# Debug-unit_rev01.net
KiCad netlist of a schematic drawn in EAGLE
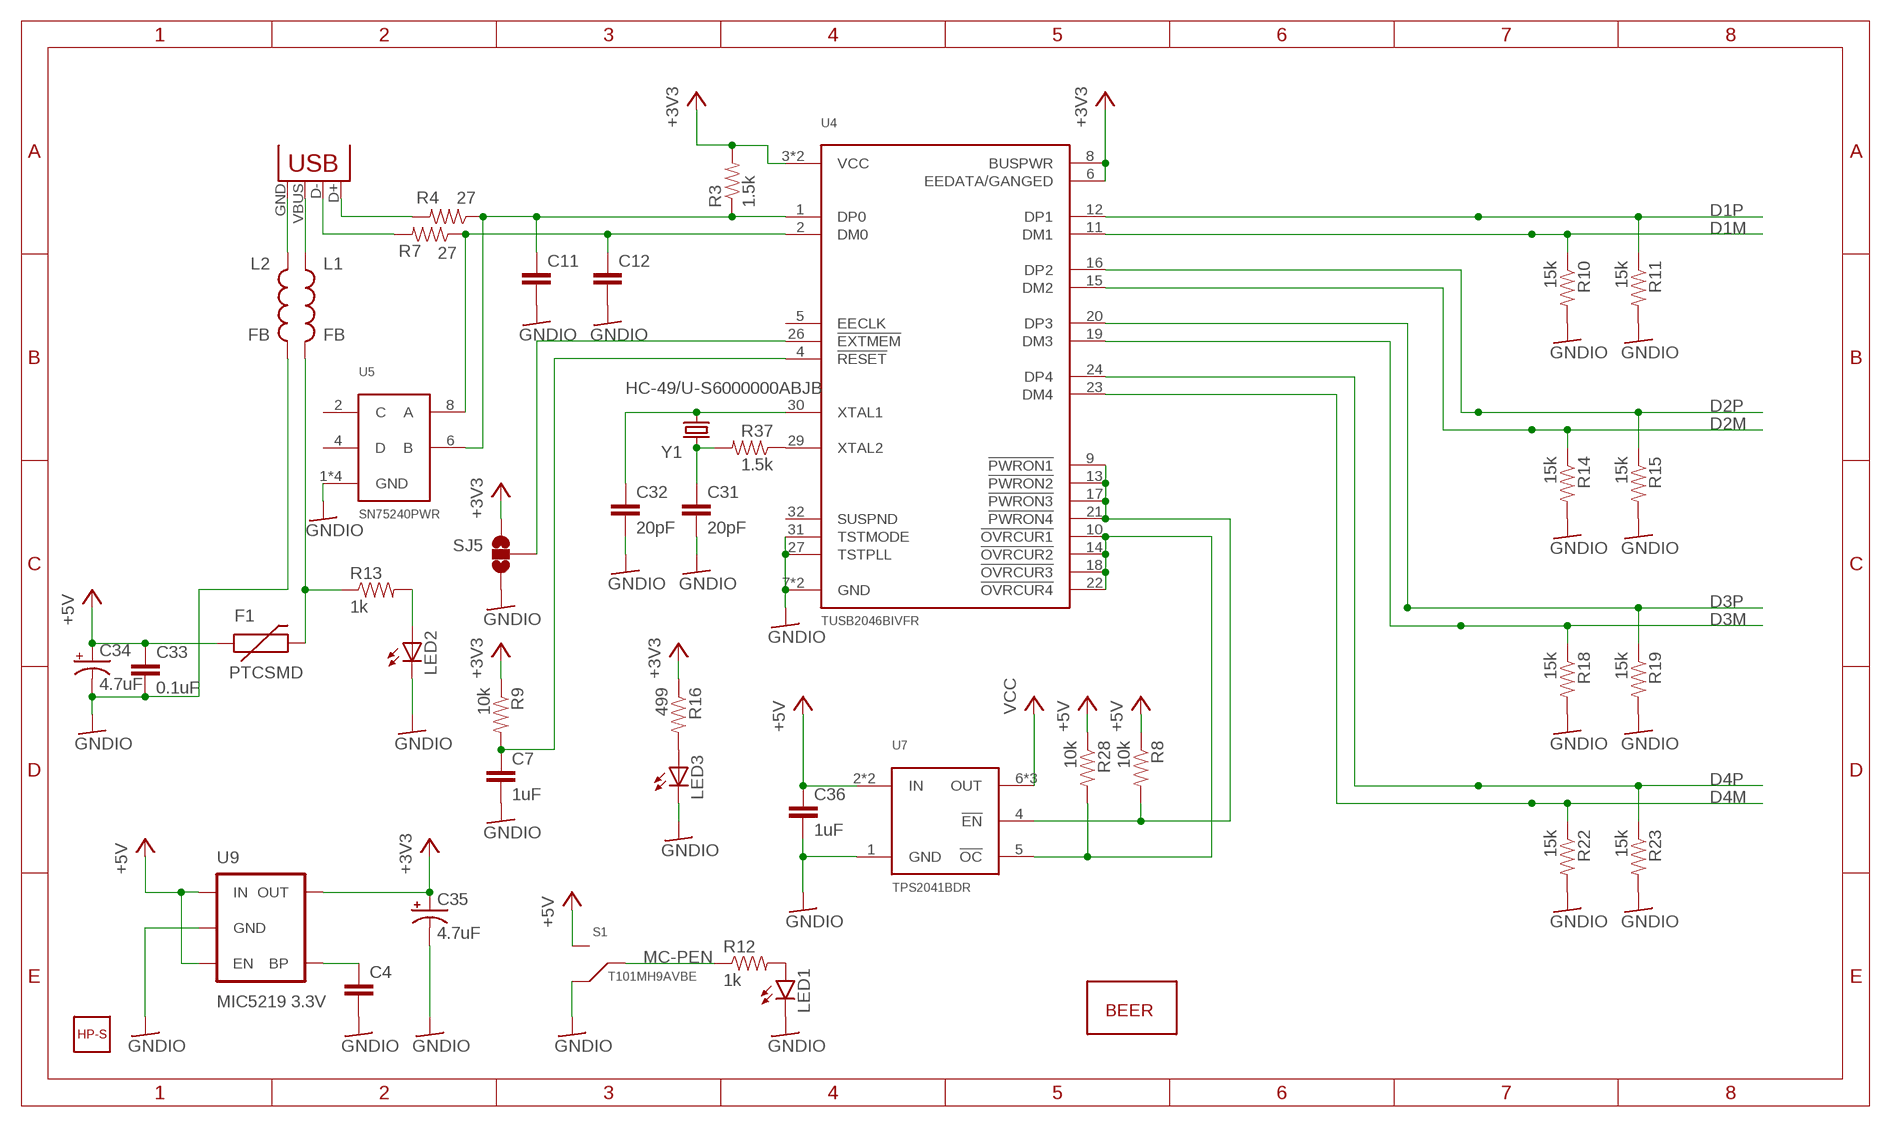
[diagram p0: schematic, sheet 1]
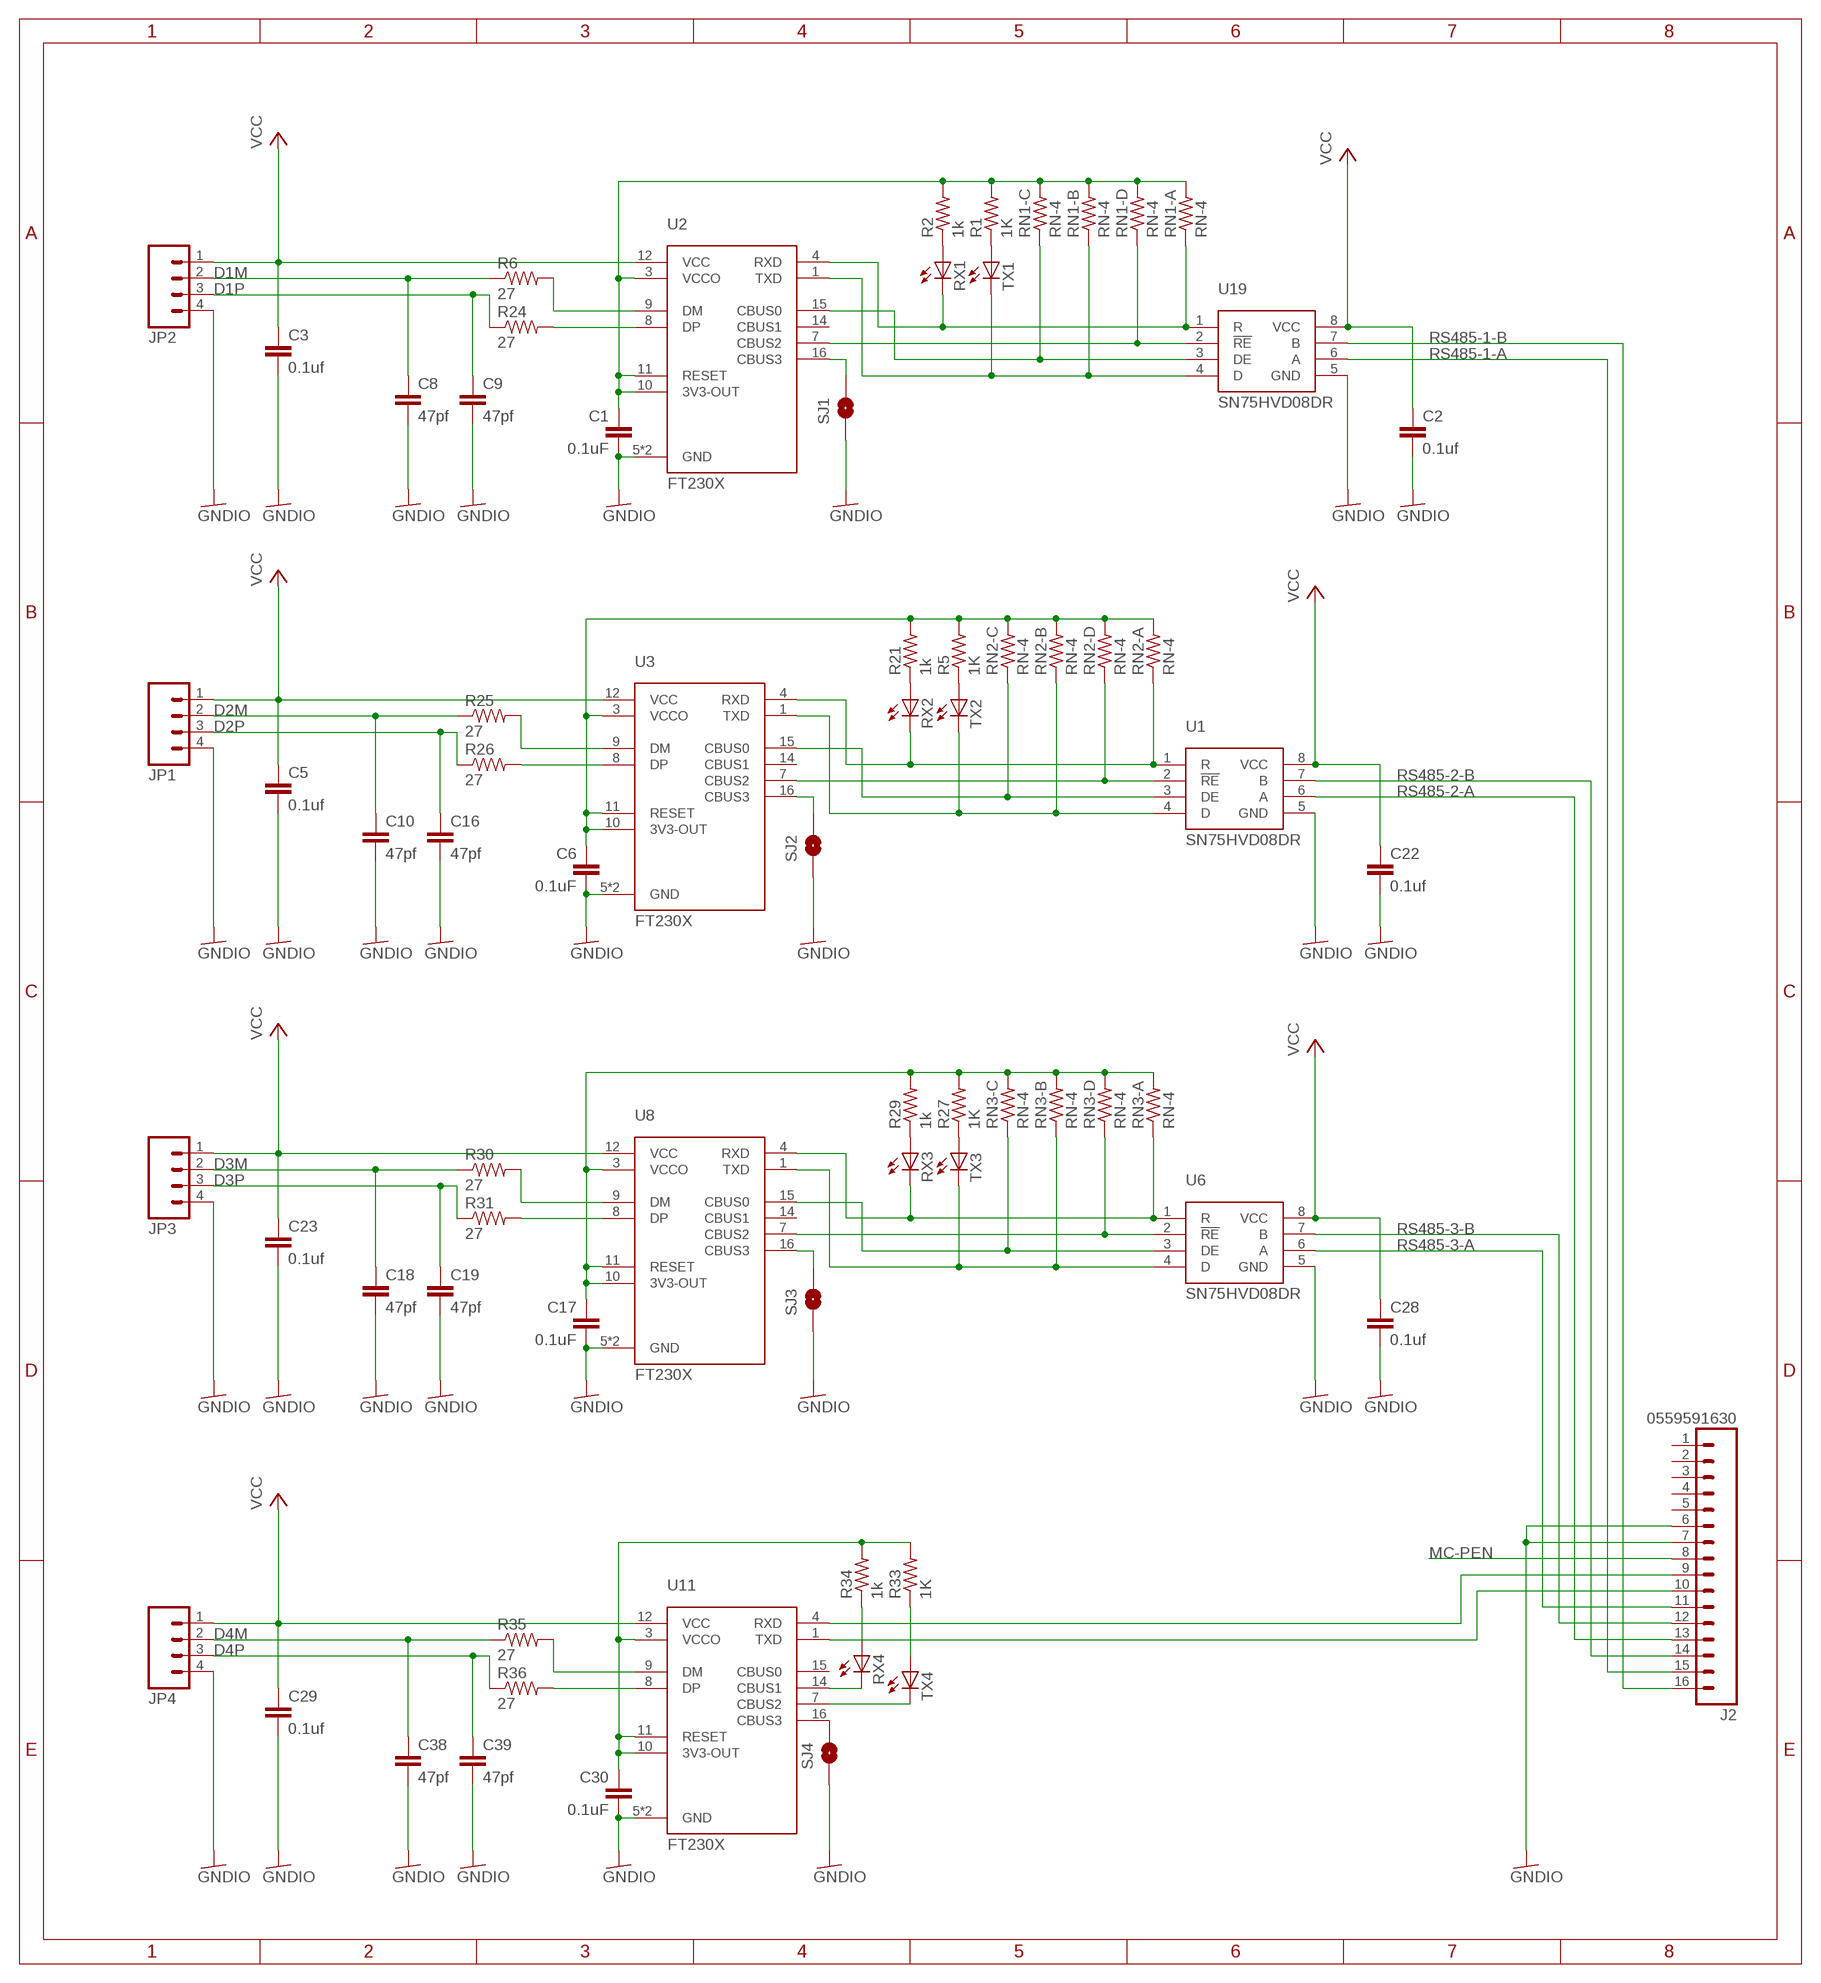
[diagram p1: schematic, sheet 2]

(export (version "E")
  (design (tool "Eeschema 10.0.6"))
  (components
    (comp (ref "C1")
      (value "0.1uF")
      (footprint "eagle-import:0805")
      (libsource (lib "eagle-import") (part "CAP0805"))
    )
    (comp (ref "C2")
      (value "0.1uf")
      (footprint "eagle-import:0805")
      (libsource (lib "eagle-import") (part "CAP0805"))
    )
    (comp (ref "C3")
      (value "0.1uf")
      (footprint "eagle-import:0805")
      (libsource (lib "eagle-import") (part "CAP0805"))
    )
    (comp (ref "C5")
      (value "0.1uf")
      (footprint "eagle-import:0805")
      (libsource (lib "eagle-import") (part "CAP0805"))
    )
    (comp (ref "C6")
      (value "0.1uF")
      (footprint "eagle-import:0805")
      (libsource (lib "eagle-import") (part "CAP0805"))
    )
    (comp (ref "C8")
      (value "47pf")
      (footprint "eagle-import:0805")
      (libsource (lib "eagle-import") (part "CAP0805"))
    )
    (comp (ref "C9")
      (value "47pf")
      (footprint "eagle-import:0805")
      (libsource (lib "eagle-import") (part "CAP0805"))
    )
    (comp (ref "C10")
      (value "47pf")
      (footprint "eagle-import:0805")
      (libsource (lib "eagle-import") (part "CAP0805"))
    )
    (comp (ref "C16")
      (value "47pf")
      (footprint "eagle-import:0805")
      (libsource (lib "eagle-import") (part "CAP0805"))
    )
    (comp (ref "C17")
      (value "0.1uF")
      (footprint "eagle-import:0805")
      (libsource (lib "eagle-import") (part "CAP0805"))
    )
    (comp (ref "C18")
      (value "47pf")
      (footprint "eagle-import:0805")
      (libsource (lib "eagle-import") (part "CAP0805"))
    )
    (comp (ref "C19")
      (value "47pf")
      (footprint "eagle-import:0805")
      (libsource (lib "eagle-import") (part "CAP0805"))
    )
    (comp (ref "C22")
      (value "0.1uf")
      (footprint "eagle-import:0805")
      (libsource (lib "eagle-import") (part "CAP0805"))
    )
    (comp (ref "C23")
      (value "0.1uf")
      (footprint "eagle-import:0805")
      (libsource (lib "eagle-import") (part "CAP0805"))
    )
    (comp (ref "C28")
      (value "0.1uf")
      (footprint "eagle-import:0805")
      (libsource (lib "eagle-import") (part "CAP0805"))
    )
    (comp (ref "C29")
      (value "0.1uf")
      (footprint "eagle-import:0805")
      (libsource (lib "eagle-import") (part "CAP0805"))
    )
    (comp (ref "C30")
      (value "0.1uF")
      (footprint "eagle-import:0805")
      (libsource (lib "eagle-import") (part "CAP0805"))
    )
    (comp (ref "C38")
      (value "47pf")
      (footprint "eagle-import:0805")
      (libsource (lib "eagle-import") (part "CAP0805"))
    )
    (comp (ref "C39")
      (value "47pf")
      (footprint "eagle-import:0805")
      (libsource (lib "eagle-import") (part "CAP0805"))
    )
    (comp (ref "J2")
      (value "0559591630")
      (footprint "eagle-import:0559591630")
      (libsource (lib "eagle-import") (part "0559591630"))
    )
    (comp (ref "JP1")
      (value "M04POLAR_LOCK")
      (footprint "eagle-import:MOLEX-1X4_LOCK")
      (libsource (lib "eagle-import") (part "M04POLAR_LOCK"))
    )
    (comp (ref "JP2")
      (value "M04POLAR_LOCK")
      (footprint "eagle-import:MOLEX-1X4_LOCK")
      (libsource (lib "eagle-import") (part "M04POLAR_LOCK"))
    )
    (comp (ref "JP3")
      (value "M04POLAR_LOCK")
      (footprint "eagle-import:MOLEX-1X4_LOCK")
      (libsource (lib "eagle-import") (part "M04POLAR_LOCK"))
    )
    (comp (ref "JP4")
      (value "M04POLAR_LOCK")
      (footprint "eagle-import:MOLEX-1X4_LOCK")
      (libsource (lib "eagle-import") (part "M04POLAR_LOCK"))
    )
    (comp (ref "R1")
      (value "1K")
      (footprint "eagle-import:R0805")
      (libsource (lib "eagle-import") (part "R-US_R0805"))
    )
    (comp (ref "R2")
      (value "1k")
      (footprint "eagle-import:R0805")
      (libsource (lib "eagle-import") (part "R-US_R0805"))
    )
    (comp (ref "R5")
      (value "1K")
      (footprint "eagle-import:R0805")
      (libsource (lib "eagle-import") (part "R-US_R0805"))
    )
    (comp (ref "R6")
      (value "27")
      (footprint "eagle-import:0805")
      (libsource (lib "eagle-import") (part "RESISTOR0805-RES"))
    )
    (comp (ref "R21")
      (value "1k")
      (footprint "eagle-import:R0805")
      (libsource (lib "eagle-import") (part "R-US_R0805"))
    )
    (comp (ref "R24")
      (value "27")
      (footprint "eagle-import:0805")
      (libsource (lib "eagle-import") (part "RESISTOR0805-RES"))
    )
    (comp (ref "R25")
      (value "27")
      (footprint "eagle-import:0805")
      (libsource (lib "eagle-import") (part "RESISTOR0805-RES"))
    )
    (comp (ref "R26")
      (value "27")
      (footprint "eagle-import:0805")
      (libsource (lib "eagle-import") (part "RESISTOR0805-RES"))
    )
    (comp (ref "R27")
      (value "1K")
      (footprint "eagle-import:R0805")
      (libsource (lib "eagle-import") (part "R-US_R0805"))
    )
    (comp (ref "R29")
      (value "1k")
      (footprint "eagle-import:R0805")
      (libsource (lib "eagle-import") (part "R-US_R0805"))
    )
    (comp (ref "R30")
      (value "27")
      (footprint "eagle-import:0805")
      (libsource (lib "eagle-import") (part "RESISTOR0805-RES"))
    )
    (comp (ref "R31")
      (value "27")
      (footprint "eagle-import:0805")
      (libsource (lib "eagle-import") (part "RESISTOR0805-RES"))
    )
    (comp (ref "R33")
      (value "1K")
      (footprint "eagle-import:R0805")
      (libsource (lib "eagle-import") (part "R-US_R0805"))
    )
    (comp (ref "R34")
      (value "1k")
      (footprint "eagle-import:R0805")
      (libsource (lib "eagle-import") (part "R-US_R0805"))
    )
    (comp (ref "R35")
      (value "27")
      (footprint "eagle-import:0805")
      (libsource (lib "eagle-import") (part "RESISTOR0805-RES"))
    )
    (comp (ref "R36")
      (value "27")
      (footprint "eagle-import:0805")
      (libsource (lib "eagle-import") (part "RESISTOR0805-RES"))
    )
    (comp (ref "RN1")
      (value "RN-4")
      (footprint "eagle-import:CRA06S")
      (libsource (lib "eagle-import") (part "RN-4"))
    )
    (comp (ref "RN2")
      (value "RN-4")
      (footprint "eagle-import:CRA06S")
      (libsource (lib "eagle-import") (part "RN-4"))
    )
    (comp (ref "RN3")
      (value "RN-4")
      (footprint "eagle-import:CRA06S")
      (libsource (lib "eagle-import") (part "RN-4"))
    )
    (comp (ref "RX1")
      (value "LEDCHIPLED_0805")
      (footprint "eagle-import:CHIPLED_0805")
      (libsource (lib "eagle-import") (part "LEDCHIPLED_0805"))
    )
    (comp (ref "RX2")
      (value "LEDCHIPLED_0805")
      (footprint "eagle-import:CHIPLED_0805")
      (libsource (lib "eagle-import") (part "LEDCHIPLED_0805"))
    )
    (comp (ref "RX3")
      (value "LEDCHIPLED_0805")
      (footprint "eagle-import:CHIPLED_0805")
      (libsource (lib "eagle-import") (part "LEDCHIPLED_0805"))
    )
    (comp (ref "RX4")
      (value "LEDCHIPLED_0805")
      (footprint "eagle-import:CHIPLED_0805")
      (libsource (lib "eagle-import") (part "LEDCHIPLED_0805"))
    )
    (comp (ref "SJ1")
      (value "JUMPER-PAD-2-NOYES_SILK")
      (footprint "eagle-import:PAD-JUMPER-2-NO_YES_SILK")
      (libsource (lib "eagle-import") (part "JUMPER-PAD-2-NOYES_SILK"))
    )
    (comp (ref "SJ2")
      (value "JUMPER-PAD-2-NOYES_SILK")
      (footprint "eagle-import:PAD-JUMPER-2-NO_YES_SILK")
      (libsource (lib "eagle-import") (part "JUMPER-PAD-2-NOYES_SILK"))
    )
    (comp (ref "SJ3")
      (value "JUMPER-PAD-2-NOYES_SILK")
      (footprint "eagle-import:PAD-JUMPER-2-NO_YES_SILK")
      (libsource (lib "eagle-import") (part "JUMPER-PAD-2-NOYES_SILK"))
    )
    (comp (ref "SJ4")
      (value "JUMPER-PAD-2-NOYES_SILK")
      (footprint "eagle-import:PAD-JUMPER-2-NO_YES_SILK")
      (libsource (lib "eagle-import") (part "JUMPER-PAD-2-NOYES_SILK"))
    )
    (comp (ref "TX1")
      (value "LEDCHIPLED_0805")
      (footprint "eagle-import:CHIPLED_0805")
      (libsource (lib "eagle-import") (part "LEDCHIPLED_0805"))
    )
    (comp (ref "TX2")
      (value "LEDCHIPLED_0805")
      (footprint "eagle-import:CHIPLED_0805")
      (libsource (lib "eagle-import") (part "LEDCHIPLED_0805"))
    )
    (comp (ref "TX3")
      (value "LEDCHIPLED_0805")
      (footprint "eagle-import:CHIPLED_0805")
      (libsource (lib "eagle-import") (part "LEDCHIPLED_0805"))
    )
    (comp (ref "TX4")
      (value "LEDCHIPLED_0805")
      (footprint "eagle-import:CHIPLED_0805")
      (libsource (lib "eagle-import") (part "LEDCHIPLED_0805"))
    )
    (comp (ref "U1")
      (value "SN75HVD08DR")
      (footprint "eagle-import:SO-8")
      (libsource (lib "eagle-import") (part "SN75HVD08DR"))
    )
    (comp (ref "U2")
      (value "FT230X")
      (footprint "eagle-import:SSOP-16")
      (libsource (lib "eagle-import") (part "FT230X"))
    )
    (comp (ref "U3")
      (value "FT230X")
      (footprint "eagle-import:SSOP-16")
      (libsource (lib "eagle-import") (part "FT230X"))
    )
    (comp (ref "U6")
      (value "SN75HVD08DR")
      (footprint "eagle-import:SO-8")
      (libsource (lib "eagle-import") (part "SN75HVD08DR"))
    )
    (comp (ref "U8")
      (value "FT230X")
      (footprint "eagle-import:SSOP-16")
      (libsource (lib "eagle-import") (part "FT230X"))
    )
    (comp (ref "U11")
      (value "FT230X")
      (footprint "eagle-import:SSOP-16")
      (libsource (lib "eagle-import") (part "FT230X"))
    )
    (comp (ref "U19")
      (value "SN75HVD08DR")
      (footprint "eagle-import:SO-8")
      (libsource (lib "eagle-import") (part "SN75HVD08DR"))
    )
    (comp (ref "C4")
      (value "CAP0805")
      (footprint "eagle-import:0805")
      (libsource (lib "eagle-import") (part "SparkFun-Passives_CAP0805"))
    )
    (comp (ref "C7")
      (value "1uF")
      (footprint "eagle-import:0805")
      (libsource (lib "eagle-import") (part "SparkFun-Passives_CAP0805"))
    )
    (comp (ref "C11")
      (value "CAP0805")
      (footprint "eagle-import:0805")
      (libsource (lib "eagle-import") (part "SparkFun-Passives_CAP0805"))
    )
    (comp (ref "C12")
      (value "CAP0805")
      (footprint "eagle-import:0805")
      (libsource (lib "eagle-import") (part "SparkFun-Passives_CAP0805"))
    )
    (comp (ref "C31")
      (value "20pF")
      (footprint "eagle-import:0805")
      (libsource (lib "eagle-import") (part "SparkFun-Passives_CAP0805"))
    )
    (comp (ref "C32")
      (value "20pF")
      (footprint "eagle-import:0805")
      (libsource (lib "eagle-import") (part "SparkFun-Passives_CAP0805"))
    )
    (comp (ref "C33")
      (value "0.1uF")
      (footprint "eagle-import:0805")
      (libsource (lib "eagle-import") (part "SparkFun-Passives_CAP0805"))
    )
    (comp (ref "C34")
      (value "4.7uF")
      (footprint "eagle-import:EIA3216")
      (libsource (lib "eagle-import") (part "CAP_POL1206"))
    )
    (comp (ref "C35")
      (value "4.7uF")
      (footprint "eagle-import:EIA3216")
      (libsource (lib "eagle-import") (part "CAP_POL1206"))
    )
    (comp (ref "C36")
      (value "1uF")
      (footprint "eagle-import:0805")
      (libsource (lib "eagle-import") (part "SparkFun-Passives_CAP0805"))
    )
    (comp (ref "F1")
      (value "PTCSMD")
      (footprint "eagle-import:PTC-1206")
      (libsource (lib "eagle-import") (part "PTCSMD"))
    )
    (comp (ref "JP9")
      (value "USB-B")
      (footprint "eagle-import:USB-B-PTH")
      (libsource (lib "eagle-import") (part "USBPTH"))
    )
    (comp (ref "L1")
      (value "FB")
      (footprint "eagle-import:0805")
      (libsource (lib "eagle-import") (part "INDUCTOR0805"))
    )
    (comp (ref "L2")
      (value "FB")
      (footprint "eagle-import:0805")
      (libsource (lib "eagle-import") (part "INDUCTOR0805"))
    )
    (comp (ref "LED1")
      (value "LED-3MM-NO_SILK")
      (footprint "eagle-import:LED3MM-NS")
      (libsource (lib "eagle-import") (part "LED-3MM-NO_SILK"))
    )
    (comp (ref "LED2")
      (value "LEDCHIP-LED0805")
      (footprint "eagle-import:CHIP-LED0805")
      (libsource (lib "eagle-import") (part "LEDCHIP-LED0805"))
    )
    (comp (ref "LED3")
      (value "LEDCHIP-LED0805")
      (footprint "eagle-import:CHIP-LED0805")
      (libsource (lib "eagle-import") (part "LEDCHIP-LED0805"))
    )
    (comp (ref "R3")
      (value "1.5k")
      (footprint "eagle-import:0805")
      (libsource (lib "eagle-import") (part "RESISTOR0805-RES"))
    )
    (comp (ref "R4")
      (value "27")
      (footprint "eagle-import:0805")
      (libsource (lib "eagle-import") (part "RESISTOR0805-RES"))
    )
    (comp (ref "R7")
      (value "27")
      (footprint "eagle-import:0805")
      (libsource (lib "eagle-import") (part "RESISTOR0805-RES"))
    )
    (comp (ref "R8")
      (value "10k")
      (footprint "eagle-import:0805")
      (libsource (lib "eagle-import") (part "RESISTOR0805-RES"))
    )
    (comp (ref "R9")
      (value "10k")
      (footprint "eagle-import:0805")
      (libsource (lib "eagle-import") (part "RESISTOR0805-RES"))
    )
    (comp (ref "R10")
      (value "15k")
      (footprint "eagle-import:0805")
      (libsource (lib "eagle-import") (part "RESISTOR0805-RES"))
    )
    (comp (ref "R11")
      (value "15k")
      (footprint "eagle-import:0805")
      (libsource (lib "eagle-import") (part "RESISTOR0805-RES"))
    )
    (comp (ref "R12")
      (value "1k")
      (footprint "eagle-import:0805")
      (libsource (lib "eagle-import") (part "RESISTOR0805-RES"))
    )
    (comp (ref "R13")
      (value "1k")
      (footprint "eagle-import:0805")
      (libsource (lib "eagle-import") (part "RESISTOR0805-RES"))
    )
    (comp (ref "R14")
      (value "15k")
      (footprint "eagle-import:0805")
      (libsource (lib "eagle-import") (part "RESISTOR0805-RES"))
    )
    (comp (ref "R15")
      (value "15k")
      (footprint "eagle-import:0805")
      (libsource (lib "eagle-import") (part "RESISTOR0805-RES"))
    )
    (comp (ref "R16")
      (value "499")
      (footprint "eagle-import:0805")
      (libsource (lib "eagle-import") (part "RESISTOR0805-RES"))
    )
    (comp (ref "R18")
      (value "15k")
      (footprint "eagle-import:0805")
      (libsource (lib "eagle-import") (part "RESISTOR0805-RES"))
    )
    (comp (ref "R19")
      (value "15k")
      (footprint "eagle-import:0805")
      (libsource (lib "eagle-import") (part "RESISTOR0805-RES"))
    )
    (comp (ref "R22")
      (value "15k")
      (footprint "eagle-import:0805")
      (libsource (lib "eagle-import") (part "RESISTOR0805-RES"))
    )
    (comp (ref "R23")
      (value "15k")
      (footprint "eagle-import:0805")
      (libsource (lib "eagle-import") (part "RESISTOR0805-RES"))
    )
    (comp (ref "R28")
      (value "10k")
      (footprint "eagle-import:0805")
      (libsource (lib "eagle-import") (part "RESISTOR0805-RES"))
    )
    (comp (ref "R37")
      (value "1.5k")
      (footprint "eagle-import:0805")
      (libsource (lib "eagle-import") (part "RESISTOR0805-RES"))
    )
    (comp (ref "S1")
      (value "T101MH9AVBE")
      (footprint "eagle-import:T101MH9AVBE")
      (libsource (lib "eagle-import") (part "T101MH9AVBE"))
    )
    (comp (ref "SJ5")
      (value "JUMPER-PAD-3-NOFULL_BOX_SILK")
      (footprint "eagle-import:PAD-JUMPER-3-NO_YES_SILK_FULL_BOX")
      (libsource (lib "eagle-import") (part "JUMPER-PAD-3-NOFULL_BOX_SILK"))
    )
    (comp (ref "U$1")
      (value "HP-3651-B")
      (footprint "eagle-import:HP-3651-B")
      (libsource (lib "eagle-import") (part "HP-3651-B"))
    )
    (comp (ref "U$3")
      (value "BEERS")
      (footprint "eagle-import:B-S")
      (libsource (lib "eagle-import") (part "BEERS"))
    )
    (comp (ref "U4")
      (value "TUSB2046BIVFR")
      (footprint "eagle-import:LQFP-32")
      (libsource (lib "eagle-import") (part "TUSB2046BIVFR"))
    )
    (comp (ref "U5")
      (value "SN75240PWR")
      (footprint "eagle-import:TSSOP-8")
      (libsource (lib "eagle-import") (part "SN75240PWR"))
    )
    (comp (ref "U7")
      (value "TPS2041BDR")
      (footprint "eagle-import:SO-8")
      (libsource (lib "eagle-import") (part "TPS2041BDR"))
    )
    (comp (ref "U9")
      (value "MIC5219 3.3V")
      (footprint "eagle-import:SOT23-5")
      (libsource (lib "eagle-import") (part "V_REG_MIC52193.3V"))
    )
    (comp (ref "Y1")
      (value "HC-49/U-S6000000ABJB")
      (footprint "eagle-import:HC49US")
      (libsource (lib "eagle-import") (part "CRYSTALHC49US"))
    )
  )
  (nets
    (net (code "1") (name "+3V3") (class "Default")
      (node (ref "C35") (pin "A") (pinfunction "+_A") (pintype "passive"))
      (node (ref "R16") (pin "1") (pinfunction "1_1") (pintype "passive"))
      (node (ref "R3") (pin "2") (pinfunction "2_2") (pintype "passive"))
      (node (ref "R9") (pin "1") (pinfunction "1_1") (pintype "passive"))
      (node (ref "SJ5") (pin "1") (pinfunction "1_1") (pintype "passive"))
      (node (ref "U4") (pin "25") (pinfunction "VCC_25") (pintype "bidirectional"))
      (node (ref "U4") (pin "3") (pinfunction "VCC_3") (pintype "bidirectional"))
      (node (ref "U4") (pin "6") (pinfunction "EEDATA/GANGED_6") (pintype "bidirectional"))
      (node (ref "U4") (pin "8") (pinfunction "BUSPWR_8") (pintype "bidirectional"))
      (node (ref "U9") (pin "5") (pinfunction "OUT_5") (pintype "passive"))
    )
    (net (code "2") (name "+5V") (class "Default")
      (node (ref "C33") (pin "1") (pinfunction "1_1") (pintype "passive"))
      (node (ref "C34") (pin "A") (pinfunction "+_A") (pintype "passive"))
      (node (ref "C36") (pin "1") (pinfunction "1_1") (pintype "passive"))
      (node (ref "F1") (pin "1") (pinfunction "1_1") (pintype "bidirectional"))
      (node (ref "R28") (pin "1") (pinfunction "1_1") (pintype "passive"))
      (node (ref "R8") (pin "1") (pinfunction "1_1") (pintype "passive"))
      (node (ref "S1") (pin "1") (pinfunction "NO_1") (pintype "bidirectional"))
      (node (ref "U7") (pin "2") (pinfunction "IN_2") (pintype "bidirectional"))
      (node (ref "U7") (pin "3") (pinfunction "IN_3") (pintype "bidirectional"))
      (node (ref "U9") (pin "1") (pinfunction "IN_1") (pintype "input"))
      (node (ref "U9") (pin "3") (pinfunction "EN_3") (pintype "input"))
    )
    (net (code "3") (name "D1M") (class "Default")
      (node (ref "C8") (pin "1") (pinfunction "1_1") (pintype "passive"))
      (node (ref "JP2") (pin "2") (pinfunction "2_2") (pintype "passive"))
      (node (ref "R10") (pin "1") (pinfunction "1_1") (pintype "passive"))
      (node (ref "R6") (pin "1") (pinfunction "1_1") (pintype "passive"))
      (node (ref "U4") (pin "11") (pinfunction "DM1_11") (pintype "bidirectional"))
    )
    (net (code "4") (name "D1P") (class "Default")
      (node (ref "C9") (pin "1") (pinfunction "1_1") (pintype "passive"))
      (node (ref "JP2") (pin "3") (pinfunction "3_3") (pintype "passive"))
      (node (ref "R11") (pin "1") (pinfunction "1_1") (pintype "passive"))
      (node (ref "R24") (pin "1") (pinfunction "1_1") (pintype "passive"))
      (node (ref "U4") (pin "12") (pinfunction "DP1_12") (pintype "bidirectional"))
    )
    (net (code "5") (name "D2M") (class "Default")
      (node (ref "C10") (pin "1") (pinfunction "1_1") (pintype "passive"))
      (node (ref "JP1") (pin "2") (pinfunction "2_2") (pintype "passive"))
      (node (ref "R14") (pin "1") (pinfunction "1_1") (pintype "passive"))
      (node (ref "R25") (pin "1") (pinfunction "1_1") (pintype "passive"))
      (node (ref "U4") (pin "15") (pinfunction "DM2_15") (pintype "bidirectional"))
    )
    (net (code "6") (name "D2P") (class "Default")
      (node (ref "C16") (pin "1") (pinfunction "1_1") (pintype "passive"))
      (node (ref "JP1") (pin "3") (pinfunction "3_3") (pintype "passive"))
      (node (ref "R15") (pin "1") (pinfunction "1_1") (pintype "passive"))
      (node (ref "R26") (pin "1") (pinfunction "1_1") (pintype "passive"))
      (node (ref "U4") (pin "16") (pinfunction "DP2_16") (pintype "bidirectional"))
    )
    (net (code "7") (name "D3M") (class "Default")
      (node (ref "C18") (pin "1") (pinfunction "1_1") (pintype "passive"))
      (node (ref "JP3") (pin "2") (pinfunction "2_2") (pintype "passive"))
      (node (ref "R18") (pin "1") (pinfunction "1_1") (pintype "passive"))
      (node (ref "R30") (pin "1") (pinfunction "1_1") (pintype "passive"))
      (node (ref "U4") (pin "19") (pinfunction "DM3_19") (pintype "bidirectional"))
    )
    (net (code "8") (name "D3P") (class "Default")
      (node (ref "C19") (pin "1") (pinfunction "1_1") (pintype "passive"))
      (node (ref "JP3") (pin "3") (pinfunction "3_3") (pintype "passive"))
      (node (ref "R19") (pin "1") (pinfunction "1_1") (pintype "passive"))
      (node (ref "R31") (pin "1") (pinfunction "1_1") (pintype "passive"))
      (node (ref "U4") (pin "20") (pinfunction "DP3_20") (pintype "bidirectional"))
    )
    (net (code "9") (name "D4M") (class "Default")
      (node (ref "C38") (pin "1") (pinfunction "1_1") (pintype "passive"))
      (node (ref "JP4") (pin "2") (pinfunction "2_2") (pintype "passive"))
      (node (ref "R22") (pin "1") (pinfunction "1_1") (pintype "passive"))
      (node (ref "R35") (pin "1") (pinfunction "1_1") (pintype "passive"))
      (node (ref "U4") (pin "23") (pinfunction "DM4_23") (pintype "bidirectional"))
    )
    (net (code "10") (name "D4P") (class "Default")
      (node (ref "C39") (pin "1") (pinfunction "1_1") (pintype "passive"))
      (node (ref "JP4") (pin "3") (pinfunction "3_3") (pintype "passive"))
      (node (ref "R23") (pin "1") (pinfunction "1_1") (pintype "passive"))
      (node (ref "R36") (pin "1") (pinfunction "1_1") (pintype "passive"))
      (node (ref "U4") (pin "24") (pinfunction "DP4_24") (pintype "bidirectional"))
    )
    (net (code "11") (name "GNDIO") (class "Default")
      (node (ref "C1") (pin "2") (pinfunction "2_2") (pintype "passive"))
      (node (ref "C10") (pin "2") (pinfunction "2_2") (pintype "passive"))
      (node (ref "C11") (pin "2") (pinfunction "2_2") (pintype "passive"))
      (node (ref "C12") (pin "2") (pinfunction "2_2") (pintype "passive"))
      (node (ref "C16") (pin "2") (pinfunction "2_2") (pintype "passive"))
      (node (ref "C17") (pin "2") (pinfunction "2_2") (pintype "passive"))
      (node (ref "C18") (pin "2") (pinfunction "2_2") (pintype "passive"))
      (node (ref "C19") (pin "2") (pinfunction "2_2") (pintype "passive"))
      (node (ref "C2") (pin "2") (pinfunction "2_2") (pintype "passive"))
      (node (ref "C22") (pin "2") (pinfunction "2_2") (pintype "passive"))
      (node (ref "C23") (pin "2") (pinfunction "2_2") (pintype "passive"))
      (node (ref "C28") (pin "2") (pinfunction "2_2") (pintype "passive"))
      (node (ref "C29") (pin "2") (pinfunction "2_2") (pintype "passive"))
      (node (ref "C3") (pin "2") (pinfunction "2_2") (pintype "passive"))
      (node (ref "C30") (pin "2") (pinfunction "2_2") (pintype "passive"))
      (node (ref "C31") (pin "2") (pinfunction "2_2") (pintype "passive"))
      (node (ref "C32") (pin "2") (pinfunction "2_2") (pintype "passive"))
      (node (ref "C33") (pin "2") (pinfunction "2_2") (pintype "passive"))
      (node (ref "C34") (pin "C") (pinfunction "-_C") (pintype "passive"))
      (node (ref "C35") (pin "C") (pinfunction "-_C") (pintype "passive"))
      (node (ref "C36") (pin "2") (pinfunction "2_2") (pintype "passive"))
      (node (ref "C38") (pin "2") (pinfunction "2_2") (pintype "passive"))
      (node (ref "C39") (pin "2") (pinfunction "2_2") (pintype "passive"))
      (node (ref "C4") (pin "2") (pinfunction "2_2") (pintype "passive"))
      (node (ref "C5") (pin "2") (pinfunction "2_2") (pintype "passive"))
      (node (ref "C6") (pin "2") (pinfunction "2_2") (pintype "passive"))
      (node (ref "C7") (pin "2") (pinfunction "2_2") (pintype "passive"))
      (node (ref "C8") (pin "2") (pinfunction "2_2") (pintype "passive"))
      (node (ref "C9") (pin "2") (pinfunction "2_2") (pintype "passive"))
      (node (ref "J2") (pin "6") (pinfunction "6_6") (pintype "passive"))
      (node (ref "J2") (pin "7") (pinfunction "7_7") (pintype "passive"))
      (node (ref "JP1") (pin "4") (pinfunction "4_4") (pintype "passive"))
      (node (ref "JP2") (pin "4") (pinfunction "4_4") (pintype "passive"))
      (node (ref "JP3") (pin "4") (pinfunction "4_4") (pintype "passive"))
      (node (ref "JP4") (pin "4") (pinfunction "4_4") (pintype "passive"))
      (node (ref "L2") (pin "2") (pinfunction "2_2") (pintype "passive"))
      (node (ref "LED1") (pin "K") (pinfunction "C_K") (pintype "passive"))
      (node (ref "LED2") (pin "C") (pinfunction "C_C") (pintype "passive"))
      (node (ref "LED3") (pin "C") (pinfunction "C_C") (pintype "passive"))
      (node (ref "R10") (pin "2") (pinfunction "2_2") (pintype "passive"))
      (node (ref "R11") (pin "2") (pinfunction "2_2") (pintype "passive"))
      (node (ref "R14") (pin "2") (pinfunction "2_2") (pintype "passive"))
      (node (ref "R15") (pin "2") (pinfunction "2_2") (pintype "passive"))
      (node (ref "R18") (pin "2") (pinfunction "2_2") (pintype "passive"))
      (node (ref "R19") (pin "2") (pinfunction "2_2") (pintype "passive"))
      (node (ref "R22") (pin "2") (pinfunction "2_2") (pintype "passive"))
      (node (ref "R23") (pin "2") (pinfunction "2_2") (pintype "passive"))
      (node (ref "S1") (pin "3") (pinfunction "NC_3") (pintype "bidirectional"))
      (node (ref "SJ1") (pin "1") (pinfunction "1_1") (pintype "passive"))
      (node (ref "SJ2") (pin "1") (pinfunction "1_1") (pintype "passive"))
      (node (ref "SJ3") (pin "1") (pinfunction "1_1") (pintype "passive"))
      (node (ref "SJ4") (pin "1") (pinfunction "1_1") (pintype "passive"))
      (node (ref "SJ5") (pin "3") (pinfunction "3_3") (pintype "passive"))
      (node (ref "U1") (pin "5") (pinfunction "GND_5") (pintype "bidirectional"))
      (node (ref "U11") (pin "13") (pinfunction "GND_13") (pintype "bidirectional"))
      (node (ref "U11") (pin "5") (pinfunction "GND_5") (pintype "bidirectional"))
      (node (ref "U19") (pin "5") (pinfunction "GND_5") (pintype "bidirectional"))
      (node (ref "U2") (pin "13") (pinfunction "GND_13") (pintype "bidirectional"))
      (node (ref "U2") (pin "5") (pinfunction "GND_5") (pintype "bidirectional"))
      (node (ref "U3") (pin "13") (pinfunction "GND_13") (pintype "bidirectional"))
      (node (ref "U3") (pin "5") (pinfunction "GND_5") (pintype "bidirectional"))
      (node (ref "U4") (pin "27") (pinfunction "TSTPLL_27") (pintype "bidirectional"))
      (node (ref "U4") (pin "28") (pinfunction "GND_28") (pintype "bidirectional"))
      (node (ref "U4") (pin "31") (pinfunction "TSTMODE_31") (pintype "bidirectional"))
      (node (ref "U4") (pin "7") (pinfunction "GND_7") (pintype "bidirectional"))
      (node (ref "U5") (pin "1") (pinfunction "GND_1") (pintype "bidirectional"))
      (node (ref "U5") (pin "3") (pinfunction "GND_3") (pintype "bidirectional"))
      (node (ref "U5") (pin "5") (pinfunction "GND_5") (pintype "bidirectional"))
      (node (ref "U5") (pin "7") (pinfunction "GND_7") (pintype "bidirectional"))
      (node (ref "U6") (pin "5") (pinfunction "GND_5") (pintype "bidirectional"))
      (node (ref "U7") (pin "1") (pinfunction "GND_1") (pintype "bidirectional"))
      (node (ref "U8") (pin "13") (pinfunction "GND_13") (pintype "bidirectional"))
      (node (ref "U8") (pin "5") (pinfunction "GND_5") (pintype "bidirectional"))
      (node (ref "U9") (pin "2") (pinfunction "GND_2") (pintype "input"))
    )
    (net (code "12") (name "MC-PEN") (class "Default")
      (node (ref "J2") (pin "8") (pinfunction "8_8") (pintype "passive"))
      (node (ref "R12") (pin "1") (pinfunction "1_1") (pintype "passive"))
      (node (ref "S1") (pin "2") (pinfunction "C_2") (pintype "bidirectional"))
    )
    (net (code "13") (name "Net-(C31-Pad1)") (class "Default")
      (node (ref "C31") (pin "1") (pinfunction "1_1") (pintype "passive"))
      (node (ref "R37") (pin "2") (pinfunction "2_2") (pintype "passive"))
      (node (ref "Y1") (pin "2") (pinfunction "2_2") (pintype "passive"))
    )
    (net (code "14") (name "Net-(F1-Pad2)") (class "Default")
      (node (ref "F1") (pin "2") (pinfunction "2_2") (pintype "bidirectional"))
      (node (ref "L1") (pin "2") (pinfunction "2_2") (pintype "passive"))
      (node (ref "R13") (pin "1") (pinfunction "1_1") (pintype "passive"))
    )
    (net (code "15") (name "Net-(JP9-PadD+)") (class "Default")
      (node (ref "JP9") (pin "D+") (pinfunction "D+_D+") (pintype "bidirectional"))
      (node (ref "R4") (pin "2") (pinfunction "2_2") (pintype "passive"))
    )
    (net (code "16") (name "Net-(JP9-PadD-)") (class "Default")
      (node (ref "JP9") (pin "D-") (pinfunction "D-_D-") (pintype "bidirectional"))
      (node (ref "R7") (pin "2") (pinfunction "2_2") (pintype "passive"))
    )
    (net (code "17") (name "Net-(JP9-PadGND)") (class "Default")
      (node (ref "JP9") (pin "GND") (pinfunction "GND_GND") (pintype "bidirectional"))
      (node (ref "L2") (pin "1") (pinfunction "1_1") (pintype "passive"))
    )
    (net (code "18") (name "Net-(JP9-PadVBUS)") (class "Default")
      (node (ref "JP9") (pin "VBUS") (pinfunction "VBUS_VBUS") (pintype "bidirectional"))
      (node (ref "L1") (pin "1") (pinfunction "1_1") (pintype "passive"))
    )
    (net (code "19") (name "Net-(LED1-PadA)") (class "Default")
      (node (ref "LED1") (pin "A") (pinfunction "A_A") (pintype "passive"))
      (node (ref "R12") (pin "2") (pinfunction "2_2") (pintype "passive"))
    )
    (net (code "20") (name "Net-(LED2-PadA)") (class "Default")
      (node (ref "LED2") (pin "A") (pinfunction "A_A") (pintype "passive"))
      (node (ref "R13") (pin "2") (pinfunction "2_2") (pintype "passive"))
    )
    (net (code "21") (name "Net-(LED3-PadA)") (class "Default")
      (node (ref "LED3") (pin "A") (pinfunction "A_A") (pintype "passive"))
      (node (ref "R16") (pin "2") (pinfunction "2_2") (pintype "passive"))
    )
    (net (code "22") (name "Net-(R1-Pad1)") (class "Default")
      (node (ref "R1") (pin "1") (pinfunction "1_1") (pintype "passive"))
      (node (ref "TX1") (pin "A") (pinfunction "A_A") (pintype "passive"))
    )
    (net (code "23") (name "Net-(R2-Pad1)") (class "Default")
      (node (ref "R2") (pin "1") (pinfunction "1_1") (pintype "passive"))
      (node (ref "RX1") (pin "A") (pinfunction "A_A") (pintype "passive"))
    )
    (net (code "24") (name "Net-(R5-Pad1)") (class "Default")
      (node (ref "R5") (pin "1") (pinfunction "1_1") (pintype "passive"))
      (node (ref "TX2") (pin "A") (pinfunction "A_A") (pintype "passive"))
    )
    (net (code "25") (name "Net-(R21-Pad1)") (class "Default")
      (node (ref "R21") (pin "1") (pinfunction "1_1") (pintype "passive"))
      (node (ref "RX2") (pin "A") (pinfunction "A_A") (pintype "passive"))
    )
    (net (code "26") (name "Net-(R27-Pad1)") (class "Default")
      (node (ref "R27") (pin "1") (pinfunction "1_1") (pintype "passive"))
      (node (ref "TX3") (pin "A") (pinfunction "A_A") (pintype "passive"))
    )
    (net (code "27") (name "Net-(R29-Pad1)") (class "Default")
      (node (ref "R29") (pin "1") (pinfunction "1_1") (pintype "passive"))
      (node (ref "RX3") (pin "A") (pinfunction "A_A") (pintype "passive"))
    )
    (net (code "28") (name "Net-(R33-Pad1)") (class "Default")
      (node (ref "R33") (pin "1") (pinfunction "1_1") (pintype "passive"))
      (node (ref "TX4") (pin "A") (pinfunction "A_A") (pintype "passive"))
    )
    (net (code "29") (name "Net-(R34-Pad1)") (class "Default")
      (node (ref "R34") (pin "1") (pinfunction "1_1") (pintype "passive"))
      (node (ref "RX4") (pin "A") (pinfunction "A_A") (pintype "passive"))
    )
    (net (code "30") (name "Net-(RN1A-2)") (class "Default")
      (node (ref "C1") (pin "1") (pinfunction "1_1") (pintype "passive"))
      (node (ref "R1") (pin "2") (pinfunction "2_2") (pintype "passive"))
      (node (ref "R2") (pin "2") (pinfunction "2_2") (pintype "passive"))
      (node (ref "RN1") (pin "5") (pinfunction "2_5") (pintype "passive"))
      (node (ref "RN1") (pin "6") (pinfunction "2_6") (pintype "passive"))
      (node (ref "RN1") (pin "7") (pinfunction "2_7") (pintype "passive"))
      (node (ref "RN1") (pin "8") (pinfunction "2_8") (pintype "passive"))
      (node (ref "U2") (pin "10") (pinfunction "3V3-OUT_10") (pintype "bidirectional"))
      (node (ref "U2") (pin "11") (pinfunction "RESET_11") (pintype "bidirectional"))
      (node (ref "U2") (pin "3") (pinfunction "VCCO_3") (pintype "bidirectional"))
    )
    (net (code "31") (name "Net-(RN1B-1)") (class "Default")
      (node (ref "RN1") (pin "2") (pinfunction "1_2") (pintype "passive"))
      (node (ref "TX1") (pin "C") (pinfunction "C_C") (pintype "passive"))
      (node (ref "U19") (pin "4") (pinfunction "D_4") (pintype "bidirectional"))
      (node (ref "U2") (pin "1") (pinfunction "TXD_1") (pintype "bidirectional"))
    )
    (net (code "32") (name "Net-(RN1C-1)") (class "Default")
      (node (ref "RN1") (pin "3") (pinfunction "1_3") (pintype "passive"))
      (node (ref "U19") (pin "3") (pinfunction "DE_3") (pintype "bidirectional"))
      (node (ref "U2") (pin "15") (pinfunction "CBUS0_15") (pintype "bidirectional"))
    )
    (net (code "33") (name "Net-(RN1D-1)") (class "Default")
      (node (ref "RN1") (pin "4") (pinfunction "1_4") (pintype "passive"))
      (node (ref "U19") (pin "2") (pinfunction "~{RE}_2") (pintype "bidirectional"))
      (node (ref "U2") (pin "7") (pinfunction "CBUS2_7") (pintype "bidirectional"))
    )
    (net (code "34") (name "Net-(RN2A-2)") (class "Default")
      (node (ref "C6") (pin "1") (pinfunction "1_1") (pintype "passive"))
      (node (ref "R21") (pin "2") (pinfunction "2_2") (pintype "passive"))
      (node (ref "R5") (pin "2") (pinfunction "2_2") (pintype "passive"))
      (node (ref "RN2") (pin "5") (pinfunction "2_5") (pintype "passive"))
      (node (ref "RN2") (pin "6") (pinfunction "2_6") (pintype "passive"))
      (node (ref "RN2") (pin "7") (pinfunction "2_7") (pintype "passive"))
      (node (ref "RN2") (pin "8") (pinfunction "2_8") (pintype "passive"))
      (node (ref "U3") (pin "10") (pinfunction "3V3-OUT_10") (pintype "bidirectional"))
      (node (ref "U3") (pin "11") (pinfunction "RESET_11") (pintype "bidirectional"))
      (node (ref "U3") (pin "3") (pinfunction "VCCO_3") (pintype "bidirectional"))
    )
    (net (code "35") (name "Net-(RN2B-1)") (class "Default")
      (node (ref "RN2") (pin "2") (pinfunction "1_2") (pintype "passive"))
      (node (ref "TX2") (pin "C") (pinfunction "C_C") (pintype "passive"))
      (node (ref "U1") (pin "4") (pinfunction "D_4") (pintype "bidirectional"))
      (node (ref "U3") (pin "1") (pinfunction "TXD_1") (pintype "bidirectional"))
    )
    (net (code "36") (name "Net-(RN2C-1)") (class "Default")
      (node (ref "RN2") (pin "3") (pinfunction "1_3") (pintype "passive"))
      (node (ref "U1") (pin "3") (pinfunction "DE_3") (pintype "bidirectional"))
      (node (ref "U3") (pin "15") (pinfunction "CBUS0_15") (pintype "bidirectional"))
    )
    (net (code "37") (name "Net-(RN2D-1)") (class "Default")
      (node (ref "RN2") (pin "4") (pinfunction "1_4") (pintype "passive"))
      (node (ref "U1") (pin "2") (pinfunction "~{RE}_2") (pintype "bidirectional"))
      (node (ref "U3") (pin "7") (pinfunction "CBUS2_7") (pintype "bidirectional"))
    )
    (net (code "38") (name "Net-(RN3A-2)") (class "Default")
      (node (ref "C17") (pin "1") (pinfunction "1_1") (pintype "passive"))
      (node (ref "R27") (pin "2") (pinfunction "2_2") (pintype "passive"))
      (node (ref "R29") (pin "2") (pinfunction "2_2") (pintype "passive"))
      (node (ref "RN3") (pin "5") (pinfunction "2_5") (pintype "passive"))
      (node (ref "RN3") (pin "6") (pinfunction "2_6") (pintype "passive"))
      (node (ref "RN3") (pin "7") (pinfunction "2_7") (pintype "passive"))
      (node (ref "RN3") (pin "8") (pinfunction "2_8") (pintype "passive"))
      (node (ref "U8") (pin "10") (pinfunction "3V3-OUT_10") (pintype "bidirectional"))
      (node (ref "U8") (pin "11") (pinfunction "RESET_11") (pintype "bidirectional"))
      (node (ref "U8") (pin "3") (pinfunction "VCCO_3") (pintype "bidirectional"))
    )
    (net (code "39") (name "Net-(RN3B-1)") (class "Default")
      (node (ref "RN3") (pin "2") (pinfunction "1_2") (pintype "passive"))
      (node (ref "TX3") (pin "C") (pinfunction "C_C") (pintype "passive"))
      (node (ref "U6") (pin "4") (pinfunction "D_4") (pintype "bidirectional"))
      (node (ref "U8") (pin "1") (pinfunction "TXD_1") (pintype "bidirectional"))
    )
    (net (code "40") (name "Net-(RN3C-1)") (class "Default")
      (node (ref "RN3") (pin "3") (pinfunction "1_3") (pintype "passive"))
      (node (ref "U6") (pin "3") (pinfunction "DE_3") (pintype "bidirectional"))
      (node (ref "U8") (pin "15") (pinfunction "CBUS0_15") (pintype "bidirectional"))
    )
    (net (code "41") (name "Net-(RN3D-1)") (class "Default")
      (node (ref "RN3") (pin "4") (pinfunction "1_4") (pintype "passive"))
      (node (ref "U6") (pin "2") (pinfunction "~{RE}_2") (pintype "bidirectional"))
      (node (ref "U8") (pin "7") (pinfunction "CBUS2_7") (pintype "bidirectional"))
    )
    (net (code "42") (name "Net-(U1-R)") (class "Default")
      (node (ref "RN2") (pin "1") (pinfunction "1_1") (pintype "passive"))
      (node (ref "RX2") (pin "C") (pinfunction "C_C") (pintype "passive"))
      (node (ref "U1") (pin "1") (pinfunction "R_1") (pintype "bidirectional"))
      (node (ref "U3") (pin "4") (pinfunction "RXD_4") (pintype "bidirectional"))
    )
    (net (code "43") (name "Net-(U2-CBUS3)") (class "Default")
      (node (ref "SJ1") (pin "2") (pinfunction "2_2") (pintype "passive"))
      (node (ref "U2") (pin "16") (pinfunction "CBUS3_16") (pintype "bidirectional"))
    )
    (net (code "44") (name "Net-(U2-DM)") (class "Default")
      (node (ref "R6") (pin "2") (pinfunction "2_2") (pintype "passive"))
      (node (ref "U2") (pin "9") (pinfunction "DM_9") (pintype "bidirectional"))
    )
    (net (code "45") (name "Net-(U2-DP)") (class "Default")
      (node (ref "R24") (pin "2") (pinfunction "2_2") (pintype "passive"))
      (node (ref "U2") (pin "8") (pinfunction "DP_8") (pintype "bidirectional"))
    )
    (net (code "46") (name "Net-(U3-CBUS3)") (class "Default")
      (node (ref "SJ2") (pin "2") (pinfunction "2_2") (pintype "passive"))
      (node (ref "U3") (pin "16") (pinfunction "CBUS3_16") (pintype "bidirectional"))
    )
    (net (code "47") (name "Net-(U3-DM)") (class "Default")
      (node (ref "R25") (pin "2") (pinfunction "2_2") (pintype "passive"))
      (node (ref "U3") (pin "9") (pinfunction "DM_9") (pintype "bidirectional"))
    )
    (net (code "48") (name "Net-(U3-DP)") (class "Default")
      (node (ref "R26") (pin "2") (pinfunction "2_2") (pintype "passive"))
      (node (ref "U3") (pin "8") (pinfunction "DP_8") (pintype "bidirectional"))
    )
    (net (code "49") (name "Net-(U4-DM0)") (class "Default")
      (node (ref "C12") (pin "1") (pinfunction "1_1") (pintype "passive"))
      (node (ref "R7") (pin "1") (pinfunction "1_1") (pintype "passive"))
      (node (ref "U4") (pin "2") (pinfunction "DM0_2") (pintype "bidirectional"))
      (node (ref "U5") (pin "8") (pinfunction "A_8") (pintype "bidirectional"))
    )
    (net (code "50") (name "Net-(U4-DP0)") (class "Default")
      (node (ref "C11") (pin "1") (pinfunction "1_1") (pintype "passive"))
      (node (ref "R3") (pin "1") (pinfunction "1_1") (pintype "passive"))
      (node (ref "R4") (pin "1") (pinfunction "1_1") (pintype "passive"))
      (node (ref "U4") (pin "1") (pinfunction "DP0_1") (pintype "bidirectional"))
      (node (ref "U5") (pin "6") (pinfunction "B_6") (pintype "bidirectional"))
    )
    (net (code "51") (name "Net-(U4-XTAL1)") (class "Default")
      (node (ref "C32") (pin "1") (pinfunction "1_1") (pintype "passive"))
      (node (ref "U4") (pin "30") (pinfunction "XTAL1_30") (pintype "bidirectional"))
      (node (ref "Y1") (pin "1") (pinfunction "1_1") (pintype "passive"))
    )
    (net (code "52") (name "Net-(U4-XTAL2)") (class "Default")
      (node (ref "R37") (pin "1") (pinfunction "1_1") (pintype "passive"))
      (node (ref "U4") (pin "29") (pinfunction "XTAL2_29") (pintype "bidirectional"))
    )
    (net (code "53") (name "Net-(U4-~{EXTMEM})") (class "Default")
      (node (ref "SJ5") (pin "2") (pinfunction "2_2") (pintype "passive"))
      (node (ref "U4") (pin "26") (pinfunction "~{EXTMEM}_26") (pintype "bidirectional"))
    )
    (net (code "54") (name "Net-(U4-~{OVRCUR1})") (class "Default")
      (node (ref "R28") (pin "2") (pinfunction "2_2") (pintype "passive"))
      (node (ref "U4") (pin "10") (pinfunction "~{OVRCUR1}_10") (pintype "bidirectional"))
      (node (ref "U4") (pin "14") (pinfunction "~{OVRCUR2}_14") (pintype "bidirectional"))
      (node (ref "U4") (pin "18") (pinfunction "~{OVRCUR3}_18") (pintype "bidirectional"))
      (node (ref "U4") (pin "22") (pinfunction "~{OVRCUR4}_22") (pintype "bidirectional"))
      (node (ref "U7") (pin "5") (pinfunction "~{OC}_5") (pintype "bidirectional"))
    )
    (net (code "55") (name "Net-(U4-~{PWRON1})") (class "Default")
      (node (ref "R8") (pin "2") (pinfunction "2_2") (pintype "passive"))
      (node (ref "U4") (pin "13") (pinfunction "~{PWRON2}_13") (pintype "bidirectional"))
      (node (ref "U4") (pin "17") (pinfunction "~{PWRON3}_17") (pintype "bidirectional"))
      (node (ref "U4") (pin "21") (pinfunction "~{PWRON4}_21") (pintype "bidirectional"))
      (node (ref "U4") (pin "9") (pinfunction "~{PWRON1}_9") (pintype "bidirectional"))
      (node (ref "U7") (pin "4") (pinfunction "~{EN}_4") (pintype "bidirectional"))
    )
    (net (code "56") (name "Net-(U4-~{RESET})") (class "Default")
      (node (ref "C7") (pin "1") (pinfunction "1_1") (pintype "passive"))
      (node (ref "R9") (pin "2") (pinfunction "2_2") (pintype "passive"))
      (node (ref "U4") (pin "4") (pinfunction "~{RESET}_4") (pintype "bidirectional"))
    )
    (net (code "57") (name "Net-(U6-R)") (class "Default")
      (node (ref "RN3") (pin "1") (pinfunction "1_1") (pintype "passive"))
      (node (ref "RX3") (pin "C") (pinfunction "C_C") (pintype "passive"))
      (node (ref "U6") (pin "1") (pinfunction "R_1") (pintype "bidirectional"))
      (node (ref "U8") (pin "4") (pinfunction "RXD_4") (pintype "bidirectional"))
    )
    (net (code "58") (name "Net-(U8-CBUS3)") (class "Default")
      (node (ref "SJ3") (pin "2") (pinfunction "2_2") (pintype "passive"))
      (node (ref "U8") (pin "16") (pinfunction "CBUS3_16") (pintype "bidirectional"))
    )
    (net (code "59") (name "Net-(U8-DM)") (class "Default")
      (node (ref "R30") (pin "2") (pinfunction "2_2") (pintype "passive"))
      (node (ref "U8") (pin "9") (pinfunction "DM_9") (pintype "bidirectional"))
    )
    (net (code "60") (name "Net-(U8-DP)") (class "Default")
      (node (ref "R31") (pin "2") (pinfunction "2_2") (pintype "passive"))
      (node (ref "U8") (pin "8") (pinfunction "DP_8") (pintype "bidirectional"))
    )
    (net (code "61") (name "Net-(U9-BP)") (class "Default")
      (node (ref "C4") (pin "1") (pinfunction "1_1") (pintype "passive"))
      (node (ref "U9") (pin "4") (pinfunction "BP_4") (pintype "input"))
    )
    (net (code "62") (name "Net-(U11-3V3-OUT)") (class "Default")
      (node (ref "C30") (pin "1") (pinfunction "1_1") (pintype "passive"))
      (node (ref "R33") (pin "2") (pinfunction "2_2") (pintype "passive"))
      (node (ref "R34") (pin "2") (pinfunction "2_2") (pintype "passive"))
      (node (ref "U11") (pin "10") (pinfunction "3V3-OUT_10") (pintype "bidirectional"))
      (node (ref "U11") (pin "11") (pinfunction "RESET_11") (pintype "bidirectional"))
      (node (ref "U11") (pin "3") (pinfunction "VCCO_3") (pintype "bidirectional"))
    )
    (net (code "63") (name "Net-(U11-CBUS1)") (class "Default")
      (node (ref "RX4") (pin "C") (pinfunction "C_C") (pintype "passive"))
      (node (ref "U11") (pin "14") (pinfunction "CBUS1_14") (pintype "bidirectional"))
    )
    (net (code "64") (name "Net-(U11-CBUS2)") (class "Default")
      (node (ref "TX4") (pin "C") (pinfunction "C_C") (pintype "passive"))
      (node (ref "U11") (pin "7") (pinfunction "CBUS2_7") (pintype "bidirectional"))
    )
    (net (code "65") (name "Net-(U11-CBUS3)") (class "Default")
      (node (ref "SJ4") (pin "2") (pinfunction "2_2") (pintype "passive"))
      (node (ref "U11") (pin "16") (pinfunction "CBUS3_16") (pintype "bidirectional"))
    )
    (net (code "66") (name "Net-(U11-DM)") (class "Default")
      (node (ref "R35") (pin "2") (pinfunction "2_2") (pintype "passive"))
      (node (ref "U11") (pin "9") (pinfunction "DM_9") (pintype "bidirectional"))
    )
    (net (code "67") (name "Net-(U11-DP)") (class "Default")
      (node (ref "R36") (pin "2") (pinfunction "2_2") (pintype "passive"))
      (node (ref "U11") (pin "8") (pinfunction "DP_8") (pintype "bidirectional"))
    )
    (net (code "68") (name "Net-(U11-RXD)") (class "Default")
      (node (ref "J2") (pin "9") (pinfunction "9_9") (pintype "passive"))
      (node (ref "U11") (pin "4") (pinfunction "RXD_4") (pintype "bidirectional"))
    )
    (net (code "69") (name "Net-(U11-TXD)") (class "Default")
      (node (ref "J2") (pin "10") (pinfunction "10_10") (pintype "passive"))
      (node (ref "U11") (pin "1") (pinfunction "TXD_1") (pintype "bidirectional"))
    )
    (net (code "70") (name "Net-(U19-R)") (class "Default")
      (node (ref "RN1") (pin "1") (pinfunction "1_1") (pintype "passive"))
      (node (ref "RX1") (pin "C") (pinfunction "C_C") (pintype "passive"))
      (node (ref "U19") (pin "1") (pinfunction "R_1") (pintype "bidirectional"))
      (node (ref "U2") (pin "4") (pinfunction "RXD_4") (pintype "bidirectional"))
    )
    (net (code "71") (name "RS485-1-A") (class "Default")
      (node (ref "J2") (pin "15") (pinfunction "15_15") (pintype "passive"))
      (node (ref "U19") (pin "6") (pinfunction "A_6") (pintype "bidirectional"))
    )
    (net (code "72") (name "RS485-1-B") (class "Default")
      (node (ref "J2") (pin "16") (pinfunction "16_16") (pintype "passive"))
      (node (ref "U19") (pin "7") (pinfunction "B_7") (pintype "bidirectional"))
    )
    (net (code "73") (name "RS485-2-A") (class "Default")
      (node (ref "J2") (pin "13") (pinfunction "13_13") (pintype "passive"))
      (node (ref "U1") (pin "6") (pinfunction "A_6") (pintype "bidirectional"))
    )
    (net (code "74") (name "RS485-2-B") (class "Default")
      (node (ref "J2") (pin "14") (pinfunction "14_14") (pintype "passive"))
      (node (ref "U1") (pin "7") (pinfunction "B_7") (pintype "bidirectional"))
    )
    (net (code "75") (name "RS485-3-A") (class "Default")
      (node (ref "J2") (pin "11") (pinfunction "11_11") (pintype "passive"))
      (node (ref "U6") (pin "6") (pinfunction "A_6") (pintype "bidirectional"))
    )
    (net (code "76") (name "RS485-3-B") (class "Default")
      (node (ref "J2") (pin "12") (pinfunction "12_12") (pintype "passive"))
      (node (ref "U6") (pin "7") (pinfunction "B_7") (pintype "bidirectional"))
    )
    (net (code "77") (name "VCC") (class "Default")
      (node (ref "C2") (pin "1") (pinfunction "1_1") (pintype "passive"))
      (node (ref "C22") (pin "1") (pinfunction "1_1") (pintype "passive"))
      (node (ref "C23") (pin "1") (pinfunction "1_1") (pintype "passive"))
      (node (ref "C28") (pin "1") (pinfunction "1_1") (pintype "passive"))
      (node (ref "C29") (pin "1") (pinfunction "1_1") (pintype "passive"))
      (node (ref "C3") (pin "1") (pinfunction "1_1") (pintype "passive"))
      (node (ref "C5") (pin "1") (pinfunction "1_1") (pintype "passive"))
      (node (ref "JP1") (pin "1") (pinfunction "1_1") (pintype "passive"))
      (node (ref "JP2") (pin "1") (pinfunction "1_1") (pintype "passive"))
      (node (ref "JP3") (pin "1") (pinfunction "1_1") (pintype "passive"))
      (node (ref "JP4") (pin "1") (pinfunction "1_1") (pintype "passive"))
      (node (ref "U1") (pin "8") (pinfunction "VCC_8") (pintype "bidirectional"))
      (node (ref "U11") (pin "12") (pinfunction "VCC_12") (pintype "bidirectional"))
      (node (ref "U19") (pin "8") (pinfunction "VCC_8") (pintype "bidirectional"))
      (node (ref "U2") (pin "12") (pinfunction "VCC_12") (pintype "bidirectional"))
      (node (ref "U3") (pin "12") (pinfunction "VCC_12") (pintype "bidirectional"))
      (node (ref "U6") (pin "8") (pinfunction "VCC_8") (pintype "bidirectional"))
      (node (ref "U7") (pin "6") (pinfunction "OUT_6") (pintype "bidirectional"))
      (node (ref "U7") (pin "7") (pinfunction "OUT_7") (pintype "bidirectional"))
      (node (ref "U7") (pin "8") (pinfunction "OUT_8") (pintype "bidirectional"))
      (node (ref "U8") (pin "12") (pinfunction "VCC_12") (pintype "bidirectional"))
    )
    (net (code "78") (name "unconnected-(J2-Pad1)") (class "Default")
      (node (ref "J2") (pin "1") (pinfunction "1_1") (pintype "passive"))
    )
    (net (code "79") (name "unconnected-(J2-Pad2)") (class "Default")
      (node (ref "J2") (pin "2") (pinfunction "2_2") (pintype "passive"))
    )
    (net (code "80") (name "unconnected-(J2-Pad3)") (class "Default")
      (node (ref "J2") (pin "3") (pinfunction "3_3") (pintype "passive"))
    )
    (net (code "81") (name "unconnected-(J2-Pad4)") (class "Default")
      (node (ref "J2") (pin "4") (pinfunction "4_4") (pintype "passive"))
    )
    (net (code "82") (name "unconnected-(J2-Pad5)") (class "Default")
      (node (ref "J2") (pin "5") (pinfunction "5_5") (pintype "passive"))
    )
    (net (code "83") (name "unconnected-(U2-CBUS1-Pad14)") (class "Default")
      (node (ref "U2") (pin "14") (pinfunction "CBUS1_14") (pintype "bidirectional"))
    )
    (net (code "84") (name "unconnected-(U3-CBUS1-Pad14)") (class "Default")
      (node (ref "U3") (pin "14") (pinfunction "CBUS1_14") (pintype "bidirectional"))
    )
    (net (code "85") (name "unconnected-(U4-EECLK-Pad5)") (class "Default")
      (node (ref "U4") (pin "5") (pinfunction "EECLK_5") (pintype "bidirectional"))
    )
    (net (code "86") (name "unconnected-(U4-SUSPND-Pad32)") (class "Default")
      (node (ref "U4") (pin "32") (pinfunction "SUSPND_32") (pintype "bidirectional"))
    )
    (net (code "87") (name "unconnected-(U5-C-Pad2)") (class "Default")
      (node (ref "U5") (pin "2") (pinfunction "C_2") (pintype "bidirectional"))
    )
    (net (code "88") (name "unconnected-(U5-D-Pad4)") (class "Default")
      (node (ref "U5") (pin "4") (pinfunction "D_4") (pintype "bidirectional"))
    )
    (net (code "89") (name "unconnected-(U8-CBUS1-Pad14)") (class "Default")
      (node (ref "U8") (pin "14") (pinfunction "CBUS1_14") (pintype "bidirectional"))
    )
    (net (code "90") (name "unconnected-(U11-CBUS0-Pad15)") (class "Default")
      (node (ref "U11") (pin "15") (pinfunction "CBUS0_15") (pintype "bidirectional"))
    )
  )
)
